# SBPB_FM_v2_3.net
KiCad netlist of a schematic drawn in EAGLE
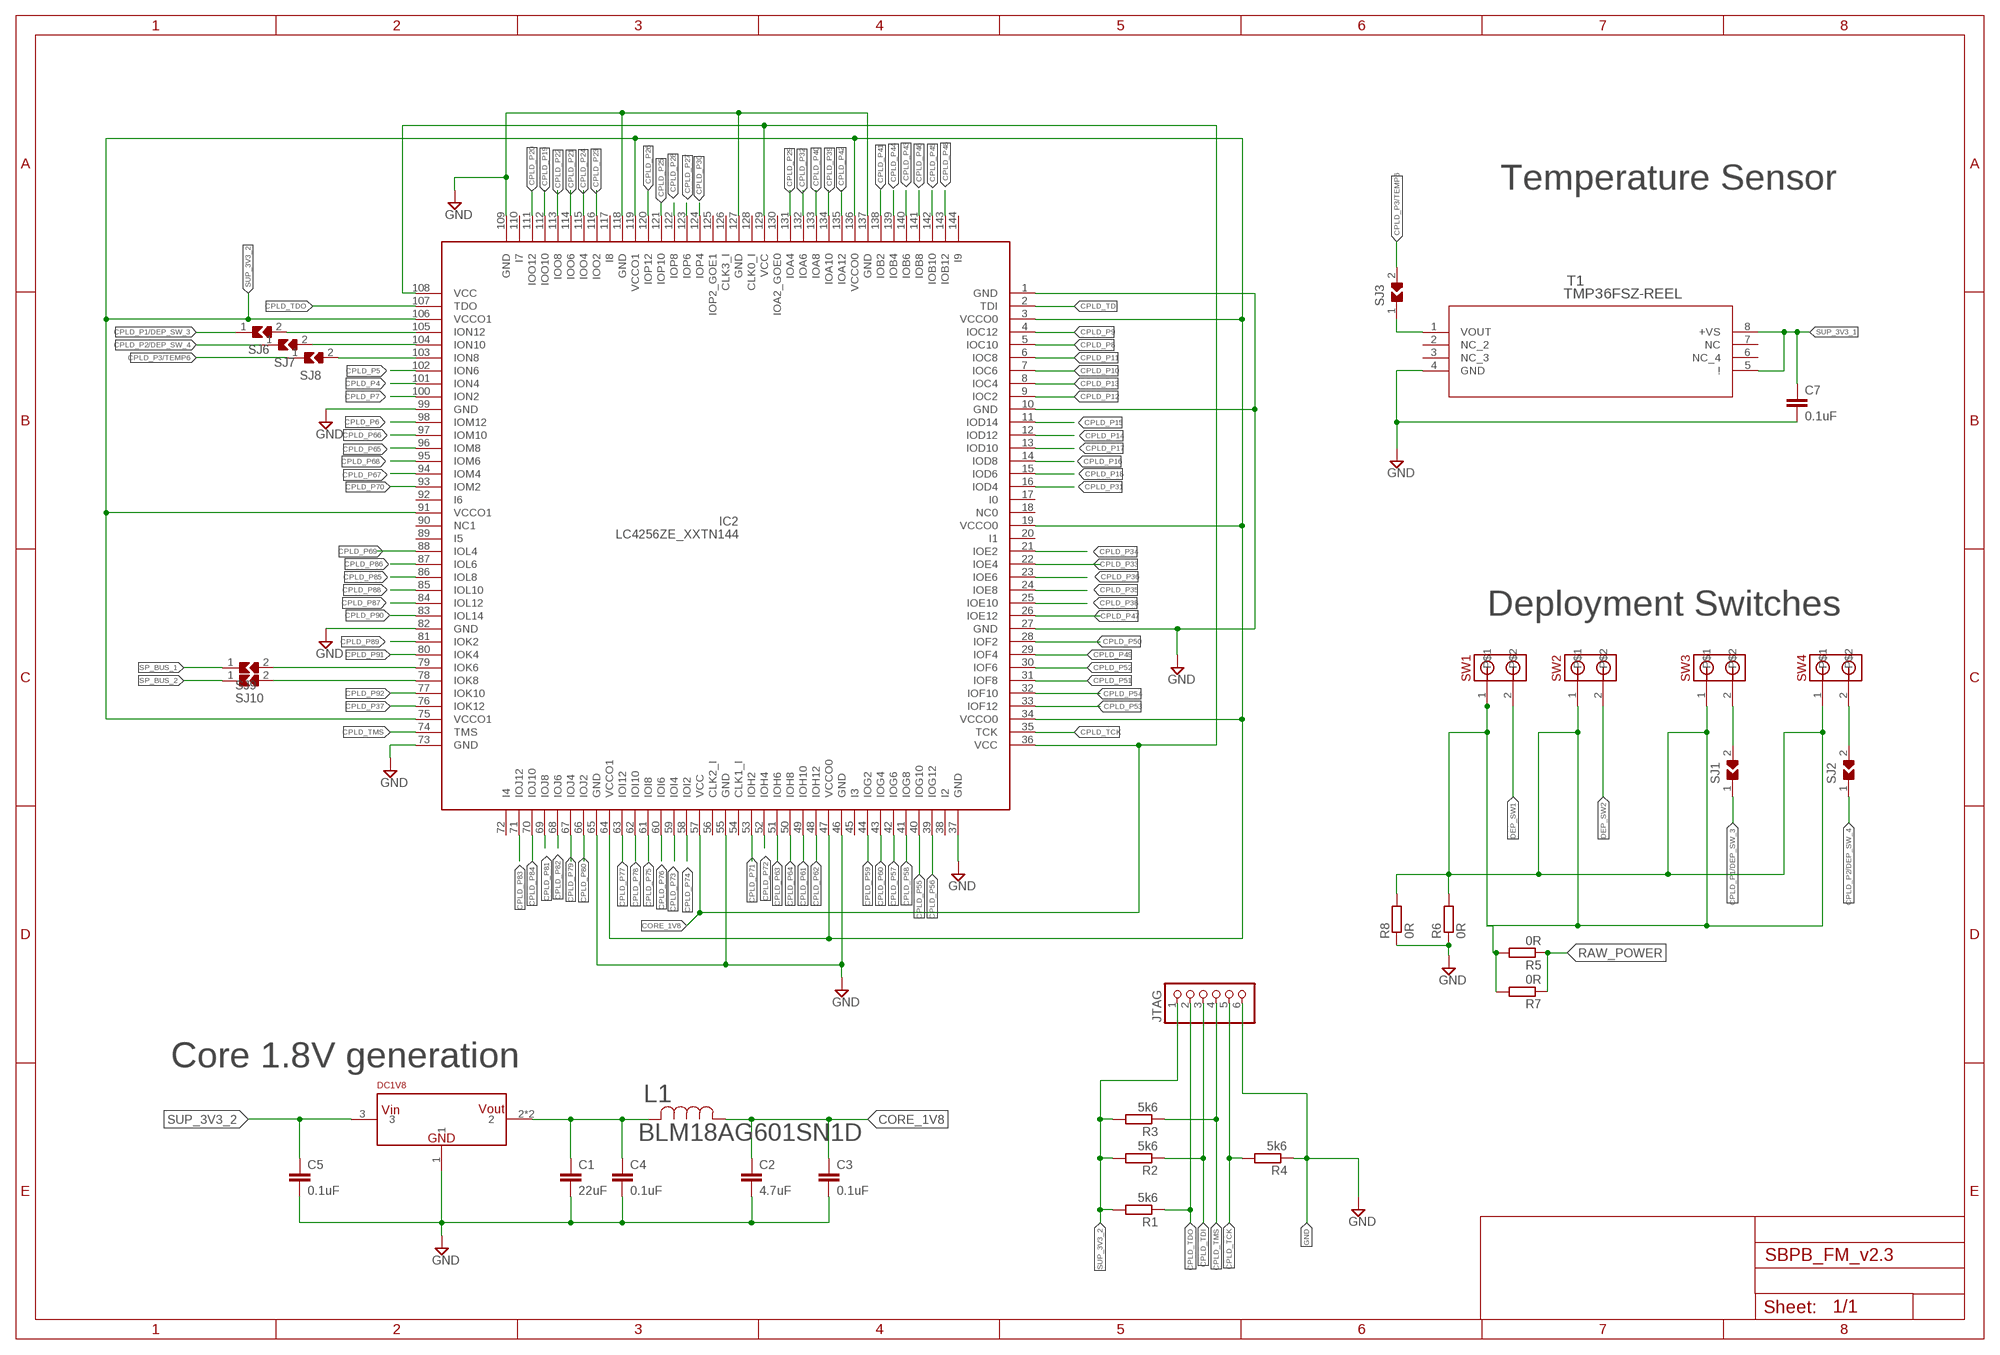
[diagram p0: schematic, sheet 1, part 1 of 2]
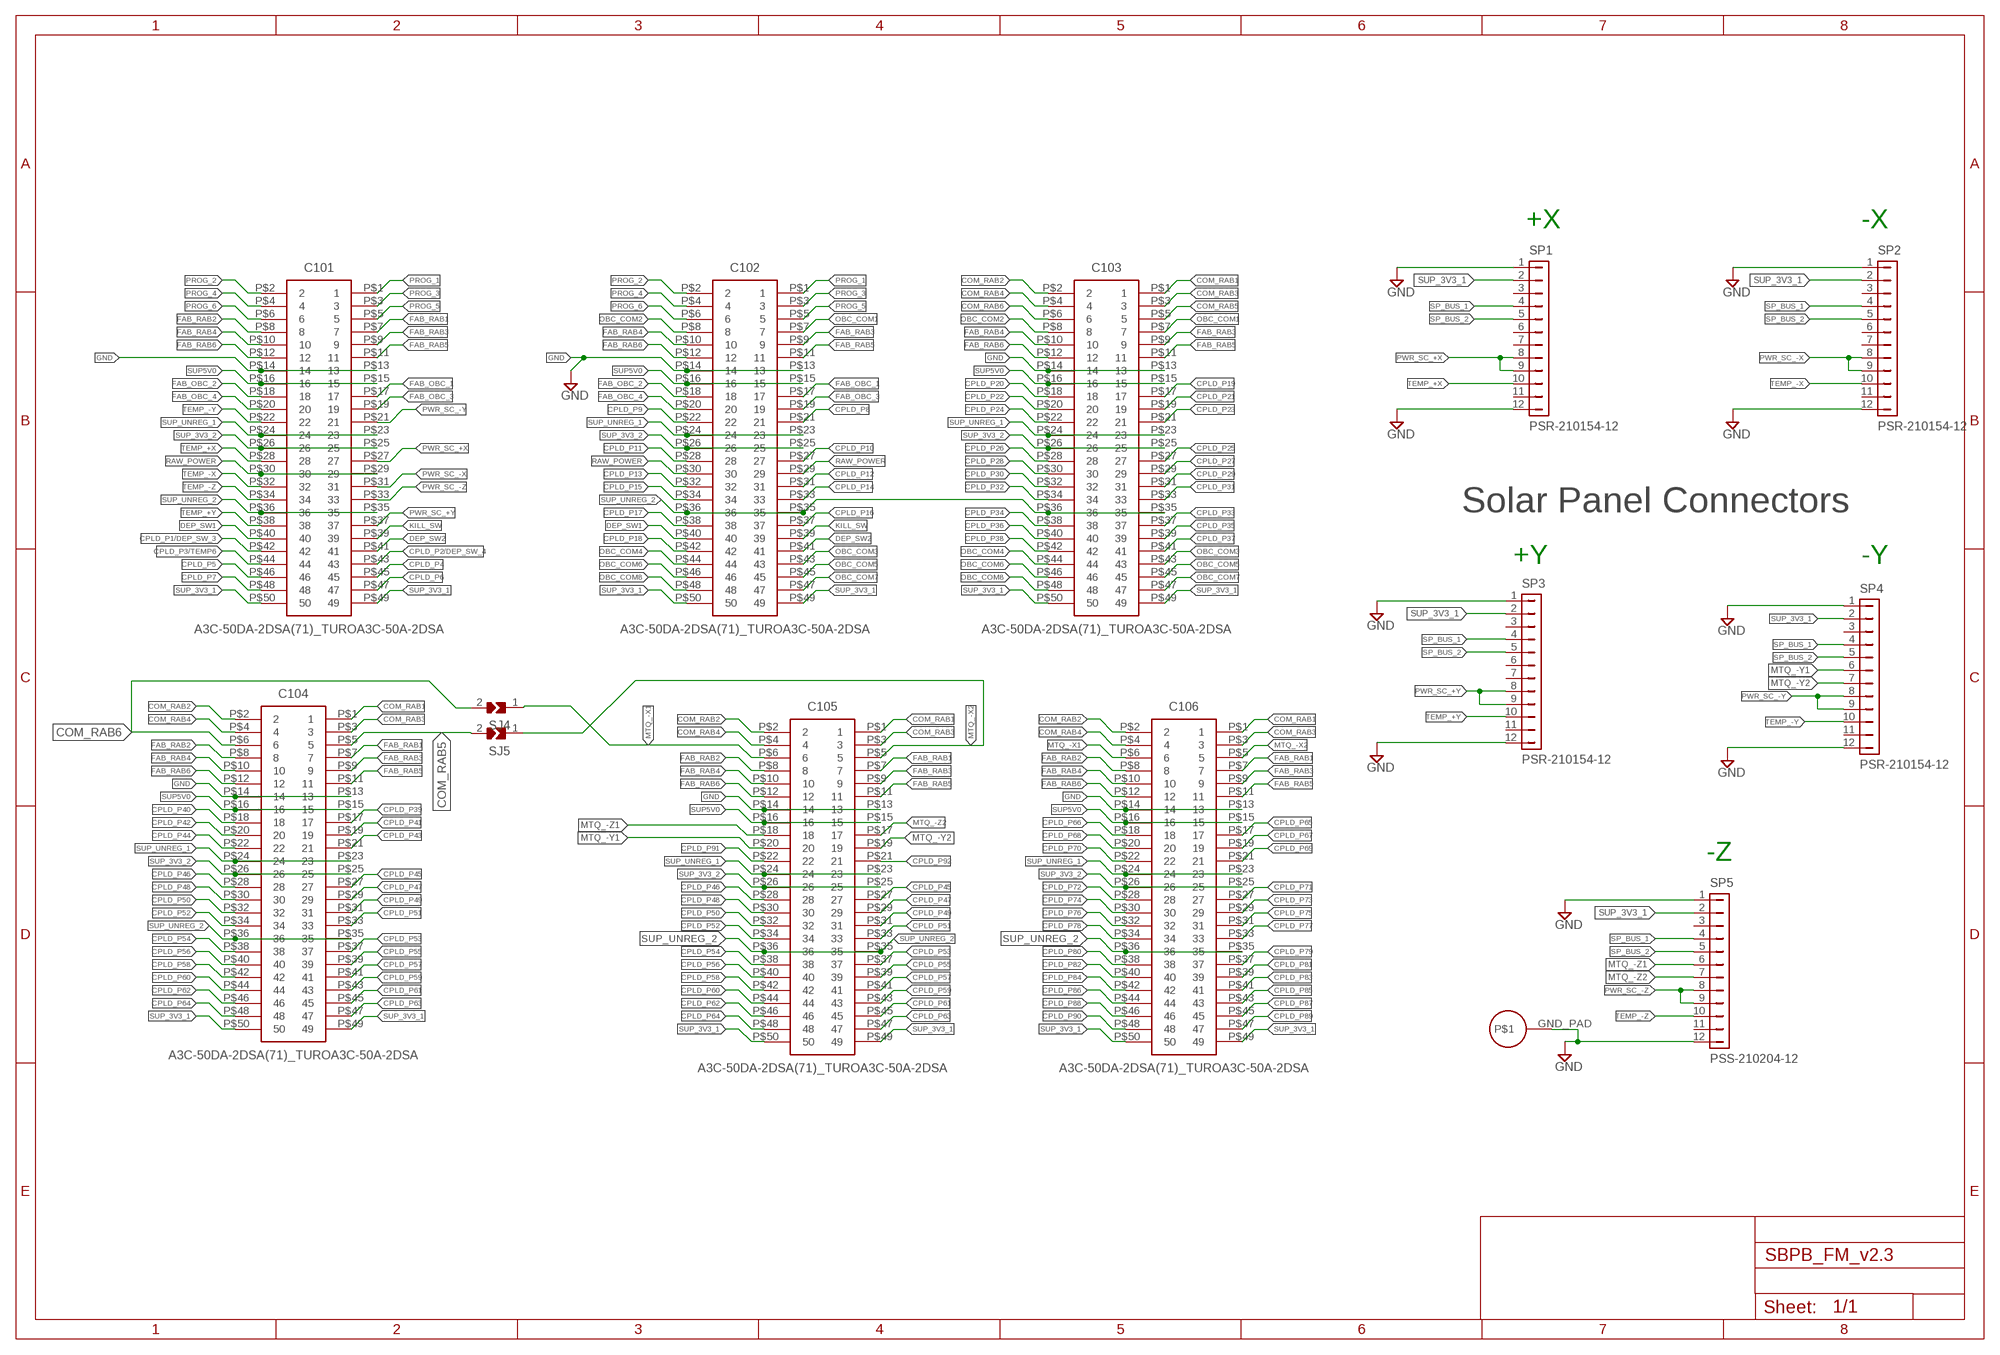
[diagram p1: schematic, sheet 1, part 2 of 2]

(export (version "E")
  (design (tool "Eeschema 10.0.6"))
  (components
    (comp (ref "C1")
      (value "22uF")
      (footprint "eagle-import:C2012")
      (libsource (lib "eagle-import") (part "CC2012"))
    )
    (comp (ref "C2")
      (value "4.7uF")
      (footprint "eagle-import:C2012")
      (libsource (lib "eagle-import") (part "CC2012"))
    )
    (comp (ref "C3")
      (value "0.1uF")
      (footprint "eagle-import:C0402")
      (libsource (lib "eagle-import") (part "CC0402"))
    )
    (comp (ref "C4")
      (value "0.1uF")
      (footprint "eagle-import:C0402")
      (libsource (lib "eagle-import") (part "CC0402"))
    )
    (comp (ref "C5")
      (value "0.1uF")
      (footprint "eagle-import:C0402")
      (libsource (lib "eagle-import") (part "CC0402"))
    )
    (comp (ref "C7")
      (value "0.1uF")
      (footprint "eagle-import:C0402")
      (libsource (lib "eagle-import") (part "CC0402"))
    )
    (comp (ref "C101")
      (value "A3C-50DA-2DSA(71)_TUROA3C-50A-2DSA")
      (footprint "eagle-import:SHDR50W60P200_2X25_5000X400X44_TR")
      (libsource (lib "eagle-import") (part "A3C-50DA-2DSA(71)_TUROA3C-50A-2DSA"))
    )
    (comp (ref "C102")
      (value "A3C-50DA-2DSA(71)_TUROA3C-50A-2DSA")
      (footprint "eagle-import:SHDR50W60P200_2X25_5000X400X44_TR")
      (libsource (lib "eagle-import") (part "A3C-50DA-2DSA(71)_TUROA3C-50A-2DSA"))
    )
    (comp (ref "C103")
      (value "A3C-50DA-2DSA(71)_TUROA3C-50A-2DSA")
      (footprint "eagle-import:SHDR50W60P200_2X25_5000X400X44_TR")
      (libsource (lib "eagle-import") (part "A3C-50DA-2DSA(71)_TUROA3C-50A-2DSA"))
    )
    (comp (ref "C104")
      (value "A3C-50DA-2DSA(71)_TUROA3C-50A-2DSA")
      (footprint "eagle-import:SHDR50W60P200_2X25_5000X400X44_TR")
      (libsource (lib "eagle-import") (part "A3C-50DA-2DSA(71)_TUROA3C-50A-2DSA"))
    )
    (comp (ref "C105")
      (value "A3C-50DA-2DSA(71)_TUROA3C-50A-2DSA")
      (footprint "eagle-import:SHDR50W60P200_2X25_5000X400X44_TR")
      (libsource (lib "eagle-import") (part "A3C-50DA-2DSA(71)_TUROA3C-50A-2DSA"))
    )
    (comp (ref "C106")
      (value "A3C-50DA-2DSA(71)_TUROA3C-50A-2DSA")
      (footprint "eagle-import:SHDR50W60P200_2X25_5000X400X44_TR")
      (libsource (lib "eagle-import") (part "A3C-50DA-2DSA(71)_TUROA3C-50A-2DSA"))
    )
    (comp (ref "DC1V8")
      (value "NCV1117ST18T3G")
      (footprint "eagle-import:SOT223")
      (libsource (lib "eagle-import") (part "NCV1117ST18T3G"))
    )
    (comp (ref "IC2")
      (value "LC4256ZE_XXTN144")
      (footprint "eagle-import:TQFP144")
      (libsource (lib "eagle-import") (part "LC4256ZE_XXTN144"))
    )
    (comp (ref "JTAG")
      (value "PINHD-1X6")
      (footprint "eagle-import:1X06")
      (libsource (lib "eagle-import") (part "PINHD-1X6"))
    )
    (comp (ref "L1")
      (value "BLM18AG601SN1D")
      (footprint "eagle-import:IND_BLM18_0603")
      (libsource (lib "eagle-import") (part "BLM18AG601SN1D"))
    )
    (comp (ref "R1")
      (value "5k6")
      (footprint "eagle-import:R0402")
      (libsource (lib "eagle-import") (part "RR0402"))
    )
    (comp (ref "R2")
      (value "5k6")
      (footprint "eagle-import:R0402")
      (libsource (lib "eagle-import") (part "RR0402"))
    )
    (comp (ref "R3")
      (value "5k6")
      (footprint "eagle-import:R0402")
      (libsource (lib "eagle-import") (part "RR0402"))
    )
    (comp (ref "R4")
      (value "5k6")
      (footprint "eagle-import:R0402")
      (libsource (lib "eagle-import") (part "RR0402"))
    )
    (comp (ref "R5")
      (value "0R")
      (footprint "eagle-import:R3216")
      (libsource (lib "eagle-import") (part "RR3216"))
    )
    (comp (ref "R6")
      (value "0R")
      (footprint "eagle-import:R3216")
      (libsource (lib "eagle-import") (part "RR3216"))
    )
    (comp (ref "R7")
      (value "0R")
      (footprint "eagle-import:R3216")
      (libsource (lib "eagle-import") (part "RR3216"))
    )
    (comp (ref "R8")
      (value "0R")
      (footprint "eagle-import:R3216")
      (libsource (lib "eagle-import") (part "RR3216"))
    )
    (comp (ref "SJ1")
      (value "SJ_BY_TURO")
      (footprint "eagle-import:SJ_TURO")
      (libsource (lib "eagle-import") (part "SJ_BY_TURO"))
    )
    (comp (ref "SJ2")
      (value "0R")
      (footprint "eagle-import:SJ_TURO")
      (libsource (lib "eagle-import") (part "SJ_BY_TURO"))
    )
    (comp (ref "SJ3")
      (value "SJ_BY_TURO")
      (footprint "eagle-import:SJ_TURO")
      (libsource (lib "eagle-import") (part "SJ_BY_TURO"))
    )
    (comp (ref "SJ4")
      (value "SJ_BY_TURO")
      (footprint "eagle-import:SJ_TURO")
      (libsource (lib "eagle-import") (part "SJ_BY_TURO"))
    )
    (comp (ref "SJ5")
      (value "SJ_BY_TURO")
      (footprint "eagle-import:SJ_TURO")
      (libsource (lib "eagle-import") (part "SJ_BY_TURO"))
    )
    (comp (ref "SJ6")
      (value "SJ_BY_TURO")
      (footprint "eagle-import:SJ_TURO")
      (libsource (lib "eagle-import") (part "SJ_BY_TURO"))
    )
    (comp (ref "SJ7")
      (value "SJ_BY_TURO")
      (footprint "eagle-import:SJ_TURO")
      (libsource (lib "eagle-import") (part "SJ_BY_TURO"))
    )
    (comp (ref "SJ8")
      (value "SJ_BY_TURO")
      (footprint "eagle-import:SJ_TURO")
      (libsource (lib "eagle-import") (part "SJ_BY_TURO"))
    )
    (comp (ref "SJ9")
      (value "SJ_BY_TURO")
      (footprint "eagle-import:SJ_TURO")
      (libsource (lib "eagle-import") (part "SJ_BY_TURO"))
    )
    (comp (ref "SJ10")
      (value "SJ_BY_TURO")
      (footprint "eagle-import:SJ_TURO")
      (libsource (lib "eagle-import") (part "SJ_BY_TURO"))
    )
    (comp (ref "SP1")
      (value "PSR-210154-12")
      (footprint "eagle-import:PIN1X12_90")
      (libsource (lib "eagle-import") (part "PSR-210154-12"))
    )
    (comp (ref "SP2")
      (value "PSR-210154-12")
      (footprint "eagle-import:PIN1X12_90")
      (libsource (lib "eagle-import") (part "PSR-210154-12"))
    )
    (comp (ref "SP3")
      (value "PSR-210154-12")
      (footprint "eagle-import:PIN1X12_90")
      (libsource (lib "eagle-import") (part "PSR-210154-12"))
    )
    (comp (ref "SP4")
      (value "PSR-210154-12")
      (footprint "eagle-import:PIN1X12_90")
      (libsource (lib "eagle-import") (part "PSR-210154-12"))
    )
    (comp (ref "SP5")
      (value "PSS-210204-12")
      (footprint "eagle-import:PIN1X12")
      (libsource (lib "eagle-import") (part "PSS-210204-12"))
    )
    (comp (ref "SW1")
      (value "MOLEX-CONN-2-0554600272")
      (footprint "eagle-import:MOLEX-CONN-2-BIRDS")
      (libsource (lib "eagle-import") (part "MOLEX-CONN-2-0554600272"))
    )
    (comp (ref "SW2")
      (value "MOLEX-CONN-2-0554600272")
      (footprint "eagle-import:MOLEX-CONN-2-BIRDS")
      (libsource (lib "eagle-import") (part "MOLEX-CONN-2-0554600272"))
    )
    (comp (ref "SW3")
      (value "MOLEX-CONN-2-0554600272")
      (footprint "eagle-import:MOLEX-CONN-2-BIRDS")
      (libsource (lib "eagle-import") (part "MOLEX-CONN-2-0554600272"))
    )
    (comp (ref "SW4")
      (value "MOLEX-CONN-2-0554600272")
      (footprint "eagle-import:MOLEX-CONN-2-BIRDS")
      (libsource (lib "eagle-import") (part "MOLEX-CONN-2-0554600272"))
    )
    (comp (ref "T1")
      (value "TMP36FSZ-REEL")
      (footprint "eagle-import:R_8")
      (fields (field (name "MANUFACTURER_PART_NUMBER") "TMP36FSZREEL"))
      (libsource (lib "eagle-import") (part "TMP36FSZ-REEL"))
    )
    (comp (ref "U$1")
      (value "GND_PAD")
      (footprint "eagle-import:GND_PAD")
      (libsource (lib "eagle-import") (part "GND_PAD"))
    )
  )
  (nets
    (net (code "1") (name "COM_RAB1") (class "Default")
      (node (ref "C103") (pin "P$1") (pinfunction "1_P$1") (pintype "passive"))
      (node (ref "C104") (pin "P$1") (pinfunction "1_P$1") (pintype "passive"))
      (node (ref "C105") (pin "P$1") (pinfunction "1_P$1") (pintype "passive"))
      (node (ref "C106") (pin "P$1") (pinfunction "1_P$1") (pintype "passive"))
    )
    (net (code "2") (name "COM_RAB2") (class "Default")
      (node (ref "C103") (pin "P$2") (pinfunction "2_P$2") (pintype "passive"))
      (node (ref "C104") (pin "P$2") (pinfunction "2_P$2") (pintype "passive"))
      (node (ref "C105") (pin "P$2") (pinfunction "2_P$2") (pintype "passive"))
      (node (ref "C106") (pin "P$2") (pinfunction "2_P$2") (pintype "passive"))
    )
    (net (code "3") (name "COM_RAB3") (class "Default")
      (node (ref "C103") (pin "P$3") (pinfunction "3_P$3") (pintype "passive"))
      (node (ref "C104") (pin "P$3") (pinfunction "3_P$3") (pintype "passive"))
      (node (ref "C105") (pin "P$3") (pinfunction "3_P$3") (pintype "passive"))
      (node (ref "C106") (pin "P$3") (pinfunction "3_P$3") (pintype "passive"))
    )
    (net (code "4") (name "COM_RAB4") (class "Default")
      (node (ref "C103") (pin "P$4") (pinfunction "4_P$4") (pintype "passive"))
      (node (ref "C104") (pin "P$4") (pinfunction "4_P$4") (pintype "passive"))
      (node (ref "C105") (pin "P$4") (pinfunction "4_P$4") (pintype "passive"))
      (node (ref "C106") (pin "P$4") (pinfunction "4_P$4") (pintype "passive"))
    )
    (net (code "5") (name "COM_RAB5") (class "Default")
      (node (ref "C103") (pin "P$5") (pinfunction "5_P$5") (pintype "passive"))
      (node (ref "C104") (pin "P$5") (pinfunction "5_P$5") (pintype "passive"))
      (node (ref "SJ5") (pin "2") (pinfunction "2_2") (pintype "passive"))
    )
    (net (code "6") (name "COM_RAB6") (class "Default")
      (node (ref "C103") (pin "P$6") (pinfunction "6_P$6") (pintype "passive"))
      (node (ref "C104") (pin "P$6") (pinfunction "6_P$6") (pintype "passive"))
      (node (ref "SJ4") (pin "2") (pinfunction "2_2") (pintype "passive"))
    )
    (net (code "7") (name "CORE_1V8") (class "Default")
      (node (ref "C2") (pin "1") (pinfunction "1_1") (pintype "passive"))
      (node (ref "C3") (pin "1") (pinfunction "1_1") (pintype "passive"))
      (node (ref "IC2") (pin "108") (pinfunction "VCC_108") (pintype "power_in"))
      (node (ref "IC2") (pin "129") (pinfunction "VCC_129") (pintype "power_in"))
      (node (ref "IC2") (pin "36") (pinfunction "VCC_36") (pintype "power_in"))
      (node (ref "IC2") (pin "57") (pinfunction "VCC_57") (pintype "power_in"))
      (node (ref "L1") (pin "1") (pinfunction "1_1") (pintype "passive"))
    )
    (net (code "8") (name "CPLD_P1{slash}DEP_SW_3") (class "Default")
      (node (ref "C101") (pin "P$42") (pinfunction "42_P$42") (pintype "passive"))
      (node (ref "SJ1") (pin "1") (pinfunction "1_1") (pintype "passive"))
      (node (ref "SJ6") (pin "1") (pinfunction "1_1") (pintype "passive"))
    )
    (net (code "9") (name "CPLD_P2{slash}DEP_SW_4") (class "Default")
      (node (ref "C101") (pin "P$43") (pinfunction "43_P$43") (pintype "passive"))
      (node (ref "SJ2") (pin "1") (pinfunction "1_1") (pintype "passive"))
      (node (ref "SJ7") (pin "1") (pinfunction "1_1") (pintype "passive"))
    )
    (net (code "10") (name "CPLD_P3{slash}TEMP6") (class "Default")
      (node (ref "C101") (pin "P$44") (pinfunction "44_P$44") (pintype "passive"))
      (node (ref "SJ3") (pin "2") (pinfunction "2_2") (pintype "passive"))
      (node (ref "SJ8") (pin "1") (pinfunction "1_1") (pintype "passive"))
    )
    (net (code "11") (name "CPLD_P4") (class "Default")
      (node (ref "C101") (pin "P$45") (pinfunction "45_P$45") (pintype "passive"))
      (node (ref "IC2") (pin "101") (pinfunction "ION4_101") (pintype "bidirectional"))
    )
    (net (code "12") (name "CPLD_P5") (class "Default")
      (node (ref "C101") (pin "P$46") (pinfunction "46_P$46") (pintype "passive"))
      (node (ref "IC2") (pin "102") (pinfunction "ION6_102") (pintype "bidirectional"))
    )
    (net (code "13") (name "CPLD_P6") (class "Default")
      (node (ref "C101") (pin "P$47") (pinfunction "47_P$47") (pintype "passive"))
      (node (ref "IC2") (pin "98") (pinfunction "IOM12_98") (pintype "bidirectional"))
    )
    (net (code "14") (name "CPLD_P7") (class "Default")
      (node (ref "C101") (pin "P$48") (pinfunction "48_P$48") (pintype "passive"))
      (node (ref "IC2") (pin "100") (pinfunction "ION2_100") (pintype "bidirectional"))
    )
    (net (code "15") (name "CPLD_P8") (class "Default")
      (node (ref "C102") (pin "P$21") (pinfunction "21_P$21") (pintype "passive"))
      (node (ref "IC2") (pin "5") (pinfunction "IOC10_5") (pintype "bidirectional"))
    )
    (net (code "16") (name "CPLD_P9") (class "Default")
      (node (ref "C102") (pin "P$22") (pinfunction "22_P$22") (pintype "passive"))
      (node (ref "IC2") (pin "4") (pinfunction "IOC12_4") (pintype "bidirectional"))
    )
    (net (code "17") (name "CPLD_P10") (class "Default")
      (node (ref "C102") (pin "P$27") (pinfunction "27_P$27") (pintype "passive"))
      (node (ref "IC2") (pin "7") (pinfunction "IOC6_7") (pintype "bidirectional"))
    )
    (net (code "18") (name "CPLD_P11") (class "Default")
      (node (ref "C102") (pin "P$28") (pinfunction "28_P$28") (pintype "passive"))
      (node (ref "IC2") (pin "6") (pinfunction "IOC8_6") (pintype "bidirectional"))
    )
    (net (code "19") (name "CPLD_P12") (class "Default")
      (node (ref "C102") (pin "P$31") (pinfunction "31_P$31") (pintype "passive"))
      (node (ref "IC2") (pin "9") (pinfunction "IOC2_9") (pintype "bidirectional"))
    )
    (net (code "20") (name "CPLD_P13") (class "Default")
      (node (ref "C102") (pin "P$32") (pinfunction "32_P$32") (pintype "passive"))
      (node (ref "IC2") (pin "8") (pinfunction "IOC4_8") (pintype "bidirectional"))
    )
    (net (code "21") (name "CPLD_P14") (class "Default")
      (node (ref "C102") (pin "P$33") (pinfunction "33_P$33") (pintype "passive"))
      (node (ref "IC2") (pin "12") (pinfunction "IOD12_12") (pintype "bidirectional"))
    )
    (net (code "22") (name "CPLD_P15") (class "Default")
      (node (ref "C102") (pin "P$34") (pinfunction "34_P$34") (pintype "passive"))
      (node (ref "IC2") (pin "11") (pinfunction "IOD14_11") (pintype "bidirectional"))
    )
    (net (code "23") (name "CPLD_P16") (class "Default")
      (node (ref "C102") (pin "P$37") (pinfunction "37_P$37") (pintype "passive"))
      (node (ref "IC2") (pin "14") (pinfunction "IOD8_14") (pintype "bidirectional"))
    )
    (net (code "24") (name "CPLD_P17") (class "Default")
      (node (ref "C102") (pin "P$38") (pinfunction "38_P$38") (pintype "passive"))
      (node (ref "IC2") (pin "13") (pinfunction "IOD10_13") (pintype "bidirectional"))
    )
    (net (code "25") (name "CPLD_P18") (class "Default")
      (node (ref "C102") (pin "P$42") (pinfunction "42_P$42") (pintype "passive"))
      (node (ref "IC2") (pin "15") (pinfunction "IOD6_15") (pintype "bidirectional"))
    )
    (net (code "26") (name "CPLD_P19") (class "Default")
      (node (ref "C103") (pin "P$17") (pinfunction "17_P$17") (pintype "passive"))
      (node (ref "IC2") (pin "112") (pinfunction "IOO10_112") (pintype "bidirectional"))
    )
    (net (code "27") (name "CPLD_P20") (class "Default")
      (node (ref "C103") (pin "P$18") (pinfunction "18_P$18") (pintype "passive"))
      (node (ref "IC2") (pin "111") (pinfunction "IOO12_111") (pintype "bidirectional"))
    )
    (net (code "28") (name "CPLD_P21") (class "Default")
      (node (ref "C103") (pin "P$19") (pinfunction "19_P$19") (pintype "passive"))
      (node (ref "IC2") (pin "114") (pinfunction "IOO6_114") (pintype "bidirectional"))
    )
    (net (code "29") (name "CPLD_P22") (class "Default")
      (node (ref "C103") (pin "P$20") (pinfunction "20_P$20") (pintype "passive"))
      (node (ref "IC2") (pin "113") (pinfunction "IOO8_113") (pintype "bidirectional"))
    )
    (net (code "30") (name "CPLD_P23") (class "Default")
      (node (ref "C103") (pin "P$21") (pinfunction "21_P$21") (pintype "passive"))
      (node (ref "IC2") (pin "116") (pinfunction "IOO2_116") (pintype "bidirectional"))
    )
    (net (code "31") (name "CPLD_P24") (class "Default")
      (node (ref "C103") (pin "P$22") (pinfunction "22_P$22") (pintype "passive"))
      (node (ref "IC2") (pin "115") (pinfunction "IOO4_115") (pintype "bidirectional"))
    )
    (net (code "32") (name "CPLD_P25") (class "Default")
      (node (ref "C103") (pin "P$27") (pinfunction "27_P$27") (pintype "passive"))
      (node (ref "IC2") (pin "121") (pinfunction "IOP10_121") (pintype "bidirectional"))
    )
    (net (code "33") (name "CPLD_P26") (class "Default")
      (node (ref "C103") (pin "P$28") (pinfunction "28_P$28") (pintype "passive"))
      (node (ref "IC2") (pin "120") (pinfunction "IOP12_120") (pintype "bidirectional"))
    )
    (net (code "34") (name "CPLD_P27") (class "Default")
      (node (ref "C103") (pin "P$29") (pinfunction "29_P$29") (pintype "passive"))
      (node (ref "IC2") (pin "123") (pinfunction "IOP6_123") (pintype "bidirectional"))
    )
    (net (code "35") (name "CPLD_P28") (class "Default")
      (node (ref "C103") (pin "P$30") (pinfunction "30_P$30") (pintype "passive"))
      (node (ref "IC2") (pin "122") (pinfunction "IOP8_122") (pintype "bidirectional"))
    )
    (net (code "36") (name "CPLD_P29") (class "Default")
      (node (ref "C103") (pin "P$31") (pinfunction "31_P$31") (pintype "passive"))
      (node (ref "IC2") (pin "131") (pinfunction "IOA4_131") (pintype "bidirectional"))
    )
    (net (code "37") (name "CPLD_P30") (class "Default")
      (node (ref "C103") (pin "P$32") (pinfunction "32_P$32") (pintype "passive"))
      (node (ref "IC2") (pin "124") (pinfunction "IOP4_124") (pintype "bidirectional"))
    )
    (net (code "38") (name "CPLD_P31") (class "Default")
      (node (ref "C103") (pin "P$33") (pinfunction "33_P$33") (pintype "passive"))
      (node (ref "IC2") (pin "16") (pinfunction "IOD4_16") (pintype "bidirectional"))
    )
    (net (code "39") (name "CPLD_P32") (class "Default")
      (node (ref "C103") (pin "P$34") (pinfunction "34_P$34") (pintype "passive"))
      (node (ref "IC2") (pin "132") (pinfunction "IOA6_132") (pintype "bidirectional"))
    )
    (net (code "40") (name "CPLD_P33") (class "Default")
      (node (ref "C103") (pin "P$37") (pinfunction "37_P$37") (pintype "passive"))
      (node (ref "IC2") (pin "22") (pinfunction "IOE4_22") (pintype "bidirectional"))
    )
    (net (code "41") (name "CPLD_P34") (class "Default")
      (node (ref "C103") (pin "P$38") (pinfunction "38_P$38") (pintype "passive"))
      (node (ref "IC2") (pin "21") (pinfunction "IOE2_21") (pintype "bidirectional"))
    )
    (net (code "42") (name "CPLD_P35") (class "Default")
      (node (ref "C103") (pin "P$39") (pinfunction "39_P$39") (pintype "passive"))
      (node (ref "IC2") (pin "24") (pinfunction "IOE8_24") (pintype "bidirectional"))
    )
    (net (code "43") (name "CPLD_P36") (class "Default")
      (node (ref "C103") (pin "P$40") (pinfunction "40_P$40") (pintype "passive"))
      (node (ref "IC2") (pin "23") (pinfunction "IOE6_23") (pintype "bidirectional"))
    )
    (net (code "44") (name "CPLD_P37") (class "Default")
      (node (ref "C103") (pin "P$41") (pinfunction "41_P$41") (pintype "passive"))
      (node (ref "IC2") (pin "76") (pinfunction "IOK12_76") (pintype "bidirectional"))
    )
    (net (code "45") (name "CPLD_P38") (class "Default")
      (node (ref "C103") (pin "P$42") (pinfunction "42_P$42") (pintype "passive"))
      (node (ref "IC2") (pin "25") (pinfunction "IOE10_25") (pintype "bidirectional"))
    )
    (net (code "46") (name "CPLD_P39") (class "Default")
      (node (ref "C104") (pin "P$17") (pinfunction "17_P$17") (pintype "passive"))
      (node (ref "IC2") (pin "134") (pinfunction "IOA10_134") (pintype "bidirectional"))
    )
    (net (code "47") (name "CPLD_P40") (class "Default")
      (node (ref "C104") (pin "P$18") (pinfunction "18_P$18") (pintype "passive"))
      (node (ref "IC2") (pin "133") (pinfunction "IOA8_133") (pintype "bidirectional"))
    )
    (net (code "48") (name "CPLD_P41") (class "Default")
      (node (ref "C104") (pin "P$19") (pinfunction "19_P$19") (pintype "passive"))
      (node (ref "IC2") (pin "138") (pinfunction "IOB2_138") (pintype "bidirectional"))
    )
    (net (code "49") (name "CPLD_P42") (class "Default")
      (node (ref "C104") (pin "P$20") (pinfunction "20_P$20") (pintype "passive"))
      (node (ref "IC2") (pin "135") (pinfunction "IOA12_135") (pintype "bidirectional"))
    )
    (net (code "50") (name "CPLD_P43") (class "Default")
      (node (ref "C104") (pin "P$21") (pinfunction "21_P$21") (pintype "passive"))
      (node (ref "IC2") (pin "140") (pinfunction "IOB6_140") (pintype "bidirectional"))
    )
    (net (code "51") (name "CPLD_P44") (class "Default")
      (node (ref "C104") (pin "P$22") (pinfunction "22_P$22") (pintype "passive"))
      (node (ref "IC2") (pin "139") (pinfunction "IOB4_139") (pintype "bidirectional"))
    )
    (net (code "52") (name "CPLD_P45") (class "Default")
      (node (ref "C104") (pin "P$27") (pinfunction "27_P$27") (pintype "passive"))
      (node (ref "C105") (pin "P$27") (pinfunction "27_P$27") (pintype "passive"))
      (node (ref "IC2") (pin "142") (pinfunction "IOB10_142") (pintype "bidirectional"))
    )
    (net (code "53") (name "CPLD_P46") (class "Default")
      (node (ref "C104") (pin "P$28") (pinfunction "28_P$28") (pintype "passive"))
      (node (ref "C105") (pin "P$28") (pinfunction "28_P$28") (pintype "passive"))
      (node (ref "IC2") (pin "141") (pinfunction "IOB8_141") (pintype "bidirectional"))
    )
    (net (code "54") (name "CPLD_P47") (class "Default")
      (node (ref "C104") (pin "P$29") (pinfunction "29_P$29") (pintype "passive"))
      (node (ref "C105") (pin "P$29") (pinfunction "29_P$29") (pintype "passive"))
      (node (ref "IC2") (pin "26") (pinfunction "IOE12_26") (pintype "bidirectional"))
    )
    (net (code "55") (name "CPLD_P48") (class "Default")
      (node (ref "C104") (pin "P$30") (pinfunction "30_P$30") (pintype "passive"))
      (node (ref "C105") (pin "P$30") (pinfunction "30_P$30") (pintype "passive"))
      (node (ref "IC2") (pin "143") (pinfunction "IOB12_143") (pintype "bidirectional"))
    )
    (net (code "56") (name "CPLD_P49") (class "Default")
      (node (ref "C104") (pin "P$31") (pinfunction "31_P$31") (pintype "passive"))
      (node (ref "C105") (pin "P$31") (pinfunction "31_P$31") (pintype "passive"))
      (node (ref "IC2") (pin "29") (pinfunction "IOF4_29") (pintype "bidirectional"))
    )
    (net (code "57") (name "CPLD_P50") (class "Default")
      (node (ref "C104") (pin "P$32") (pinfunction "32_P$32") (pintype "passive"))
      (node (ref "C105") (pin "P$32") (pinfunction "32_P$32") (pintype "passive"))
      (node (ref "IC2") (pin "28") (pinfunction "IOF2_28") (pintype "bidirectional"))
    )
    (net (code "58") (name "CPLD_P51") (class "Default")
      (node (ref "C104") (pin "P$33") (pinfunction "33_P$33") (pintype "passive"))
      (node (ref "C105") (pin "P$33") (pinfunction "33_P$33") (pintype "passive"))
      (node (ref "IC2") (pin "31") (pinfunction "IOF8_31") (pintype "bidirectional"))
    )
    (net (code "59") (name "CPLD_P52") (class "Default")
      (node (ref "C104") (pin "P$34") (pinfunction "34_P$34") (pintype "passive"))
      (node (ref "C105") (pin "P$34") (pinfunction "34_P$34") (pintype "passive"))
      (node (ref "IC2") (pin "30") (pinfunction "IOF6_30") (pintype "bidirectional"))
    )
    (net (code "60") (name "CPLD_P53") (class "Default")
      (node (ref "C104") (pin "P$37") (pinfunction "37_P$37") (pintype "passive"))
      (node (ref "C105") (pin "P$37") (pinfunction "37_P$37") (pintype "passive"))
      (node (ref "IC2") (pin "33") (pinfunction "IOF12_33") (pintype "bidirectional"))
    )
    (net (code "61") (name "CPLD_P54") (class "Default")
      (node (ref "C104") (pin "P$38") (pinfunction "38_P$38") (pintype "passive"))
      (node (ref "C105") (pin "P$38") (pinfunction "38_P$38") (pintype "passive"))
      (node (ref "IC2") (pin "32") (pinfunction "IOF10_32") (pintype "bidirectional"))
    )
    (net (code "62") (name "CPLD_P55") (class "Default")
      (node (ref "C104") (pin "P$39") (pinfunction "39_P$39") (pintype "passive"))
      (node (ref "C105") (pin "P$39") (pinfunction "39_P$39") (pintype "passive"))
      (node (ref "IC2") (pin "40") (pinfunction "IOG10_40") (pintype "bidirectional"))
    )
    (net (code "63") (name "CPLD_P56") (class "Default")
      (node (ref "C104") (pin "P$40") (pinfunction "40_P$40") (pintype "passive"))
      (node (ref "C105") (pin "P$40") (pinfunction "40_P$40") (pintype "passive"))
      (node (ref "IC2") (pin "39") (pinfunction "IOG12_39") (pintype "bidirectional"))
    )
    (net (code "64") (name "CPLD_P57") (class "Default")
      (node (ref "C104") (pin "P$41") (pinfunction "41_P$41") (pintype "passive"))
      (node (ref "C105") (pin "P$41") (pinfunction "41_P$41") (pintype "passive"))
      (node (ref "IC2") (pin "42") (pinfunction "IOG6_42") (pintype "bidirectional"))
    )
    (net (code "65") (name "CPLD_P58") (class "Default")
      (node (ref "C104") (pin "P$42") (pinfunction "42_P$42") (pintype "passive"))
      (node (ref "C105") (pin "P$42") (pinfunction "42_P$42") (pintype "passive"))
      (node (ref "IC2") (pin "41") (pinfunction "IOG8_41") (pintype "bidirectional"))
    )
    (net (code "66") (name "CPLD_P59") (class "Default")
      (node (ref "C104") (pin "P$43") (pinfunction "43_P$43") (pintype "passive"))
      (node (ref "C105") (pin "P$43") (pinfunction "43_P$43") (pintype "passive"))
      (node (ref "IC2") (pin "44") (pinfunction "IOG2_44") (pintype "bidirectional"))
    )
    (net (code "67") (name "CPLD_P60") (class "Default")
      (node (ref "C104") (pin "P$44") (pinfunction "44_P$44") (pintype "passive"))
      (node (ref "C105") (pin "P$44") (pinfunction "44_P$44") (pintype "passive"))
      (node (ref "IC2") (pin "43") (pinfunction "IOG4_43") (pintype "bidirectional"))
    )
    (net (code "68") (name "CPLD_P61") (class "Default")
      (node (ref "C104") (pin "P$45") (pinfunction "45_P$45") (pintype "passive"))
      (node (ref "C105") (pin "P$45") (pinfunction "45_P$45") (pintype "passive"))
      (node (ref "IC2") (pin "49") (pinfunction "IOH10_49") (pintype "bidirectional"))
    )
    (net (code "69") (name "CPLD_P62") (class "Default")
      (node (ref "C104") (pin "P$46") (pinfunction "46_P$46") (pintype "passive"))
      (node (ref "C105") (pin "P$46") (pinfunction "46_P$46") (pintype "passive"))
      (node (ref "IC2") (pin "48") (pinfunction "IOH12_48") (pintype "bidirectional"))
    )
    (net (code "70") (name "CPLD_P63") (class "Default")
      (node (ref "C104") (pin "P$47") (pinfunction "47_P$47") (pintype "passive"))
      (node (ref "C105") (pin "P$47") (pinfunction "47_P$47") (pintype "passive"))
      (node (ref "IC2") (pin "51") (pinfunction "IOH6_51") (pintype "bidirectional"))
    )
    (net (code "71") (name "CPLD_P64") (class "Default")
      (node (ref "C104") (pin "P$48") (pinfunction "48_P$48") (pintype "passive"))
      (node (ref "C105") (pin "P$48") (pinfunction "48_P$48") (pintype "passive"))
      (node (ref "IC2") (pin "50") (pinfunction "IOH8_50") (pintype "bidirectional"))
    )
    (net (code "72") (name "CPLD_P65") (class "Default")
      (node (ref "C106") (pin "P$17") (pinfunction "17_P$17") (pintype "passive"))
      (node (ref "IC2") (pin "96") (pinfunction "IOM8_96") (pintype "bidirectional"))
    )
    (net (code "73") (name "CPLD_P66") (class "Default")
      (node (ref "C106") (pin "P$18") (pinfunction "18_P$18") (pintype "passive"))
      (node (ref "IC2") (pin "97") (pinfunction "IOM10_97") (pintype "bidirectional"))
    )
    (net (code "74") (name "CPLD_P67") (class "Default")
      (node (ref "C106") (pin "P$19") (pinfunction "19_P$19") (pintype "passive"))
      (node (ref "IC2") (pin "94") (pinfunction "IOM4_94") (pintype "bidirectional"))
    )
    (net (code "75") (name "CPLD_P68") (class "Default")
      (node (ref "C106") (pin "P$20") (pinfunction "20_P$20") (pintype "passive"))
      (node (ref "IC2") (pin "95") (pinfunction "IOM6_95") (pintype "bidirectional"))
    )
    (net (code "76") (name "CPLD_P69") (class "Default")
      (node (ref "C106") (pin "P$21") (pinfunction "21_P$21") (pintype "passive"))
      (node (ref "IC2") (pin "88") (pinfunction "IOL4_88") (pintype "bidirectional"))
    )
    (net (code "77") (name "CPLD_P70") (class "Default")
      (node (ref "C106") (pin "P$22") (pinfunction "22_P$22") (pintype "passive"))
      (node (ref "IC2") (pin "93") (pinfunction "IOM2_93") (pintype "bidirectional"))
    )
    (net (code "78") (name "CPLD_P71") (class "Default")
      (node (ref "C106") (pin "P$27") (pinfunction "27_P$27") (pintype "passive"))
      (node (ref "IC2") (pin "53") (pinfunction "IOH2_53") (pintype "bidirectional"))
    )
    (net (code "79") (name "CPLD_P72") (class "Default")
      (node (ref "C106") (pin "P$28") (pinfunction "28_P$28") (pintype "passive"))
      (node (ref "IC2") (pin "52") (pinfunction "IOH4_52") (pintype "bidirectional"))
    )
    (net (code "80") (name "CPLD_P73") (class "Default")
      (node (ref "C106") (pin "P$29") (pinfunction "29_P$29") (pintype "passive"))
      (node (ref "IC2") (pin "59") (pinfunction "IOI4_59") (pintype "bidirectional"))
    )
    (net (code "81") (name "CPLD_P74") (class "Default")
      (node (ref "C106") (pin "P$30") (pinfunction "30_P$30") (pintype "passive"))
      (node (ref "IC2") (pin "58") (pinfunction "IOI2_58") (pintype "bidirectional"))
    )
    (net (code "82") (name "CPLD_P75") (class "Default")
      (node (ref "C106") (pin "P$31") (pinfunction "31_P$31") (pintype "passive"))
      (node (ref "IC2") (pin "61") (pinfunction "IOI8_61") (pintype "bidirectional"))
    )
    (net (code "83") (name "CPLD_P76") (class "Default")
      (node (ref "C106") (pin "P$32") (pinfunction "32_P$32") (pintype "passive"))
      (node (ref "IC2") (pin "60") (pinfunction "IOI6_60") (pintype "bidirectional"))
    )
    (net (code "84") (name "CPLD_P77") (class "Default")
      (node (ref "C106") (pin "P$33") (pinfunction "33_P$33") (pintype "passive"))
      (node (ref "IC2") (pin "63") (pinfunction "IOI12_63") (pintype "bidirectional"))
    )
    (net (code "85") (name "CPLD_P78") (class "Default")
      (node (ref "C106") (pin "P$34") (pinfunction "34_P$34") (pintype "passive"))
      (node (ref "IC2") (pin "62") (pinfunction "IOI10_62") (pintype "bidirectional"))
    )
    (net (code "86") (name "CPLD_P79") (class "Default")
      (node (ref "C106") (pin "P$37") (pinfunction "37_P$37") (pintype "passive"))
      (node (ref "IC2") (pin "67") (pinfunction "IOJ4_67") (pintype "bidirectional"))
    )
    (net (code "87") (name "CPLD_P80") (class "Default")
      (node (ref "C106") (pin "P$38") (pinfunction "38_P$38") (pintype "passive"))
      (node (ref "IC2") (pin "66") (pinfunction "IOJ2_66") (pintype "bidirectional"))
    )
    (net (code "88") (name "CPLD_P81") (class "Default")
      (node (ref "C106") (pin "P$39") (pinfunction "39_P$39") (pintype "passive"))
      (node (ref "IC2") (pin "69") (pinfunction "IOJ8_69") (pintype "bidirectional"))
    )
    (net (code "89") (name "CPLD_P82") (class "Default")
      (node (ref "C106") (pin "P$40") (pinfunction "40_P$40") (pintype "passive"))
      (node (ref "IC2") (pin "68") (pinfunction "IOJ6_68") (pintype "bidirectional"))
    )
    (net (code "90") (name "CPLD_P83") (class "Default")
      (node (ref "C106") (pin "P$41") (pinfunction "41_P$41") (pintype "passive"))
      (node (ref "IC2") (pin "71") (pinfunction "IOJ12_71") (pintype "bidirectional"))
    )
    (net (code "91") (name "CPLD_P84") (class "Default")
      (node (ref "C106") (pin "P$42") (pinfunction "42_P$42") (pintype "passive"))
      (node (ref "IC2") (pin "70") (pinfunction "IOJ10_70") (pintype "bidirectional"))
    )
    (net (code "92") (name "CPLD_P85") (class "Default")
      (node (ref "C106") (pin "P$43") (pinfunction "43_P$43") (pintype "passive"))
      (node (ref "IC2") (pin "86") (pinfunction "IOL8_86") (pintype "bidirectional"))
    )
    (net (code "93") (name "CPLD_P86") (class "Default")
      (node (ref "C106") (pin "P$44") (pinfunction "44_P$44") (pintype "passive"))
      (node (ref "IC2") (pin "87") (pinfunction "IOL6_87") (pintype "bidirectional"))
    )
    (net (code "94") (name "CPLD_P87") (class "Default")
      (node (ref "C106") (pin "P$45") (pinfunction "45_P$45") (pintype "passive"))
      (node (ref "IC2") (pin "84") (pinfunction "IOL12_84") (pintype "bidirectional"))
    )
    (net (code "95") (name "CPLD_P88") (class "Default")
      (node (ref "C106") (pin "P$46") (pinfunction "46_P$46") (pintype "passive"))
      (node (ref "IC2") (pin "85") (pinfunction "IOL10_85") (pintype "bidirectional"))
    )
    (net (code "96") (name "CPLD_P89") (class "Default")
      (node (ref "C106") (pin "P$47") (pinfunction "47_P$47") (pintype "passive"))
      (node (ref "IC2") (pin "81") (pinfunction "IOK2_81") (pintype "bidirectional"))
    )
    (net (code "97") (name "CPLD_P90") (class "Default")
      (node (ref "C106") (pin "P$48") (pinfunction "48_P$48") (pintype "passive"))
      (node (ref "IC2") (pin "83") (pinfunction "IOL14_83") (pintype "bidirectional"))
    )
    (net (code "98") (name "CPLD_P91") (class "Default")
      (node (ref "C105") (pin "P$22") (pinfunction "22_P$22") (pintype "passive"))
      (node (ref "IC2") (pin "80") (pinfunction "IOK4_80") (pintype "bidirectional"))
    )
    (net (code "99") (name "CPLD_P92") (class "Default")
      (node (ref "C105") (pin "P$21") (pinfunction "21_P$21") (pintype "passive"))
      (node (ref "IC2") (pin "77") (pinfunction "IOK10_77") (pintype "bidirectional"))
    )
    (net (code "100") (name "CPLD_TCK") (class "Default")
      (node (ref "IC2") (pin "35") (pinfunction "TCK_35") (pintype "input"))
      (node (ref "JTAG") (pin "5") (pinfunction "5_5") (pintype "passive"))
      (node (ref "R4") (pin "2") (pinfunction "2_2") (pintype "passive"))
    )
    (net (code "101") (name "CPLD_TDI") (class "Default")
      (node (ref "IC2") (pin "2") (pinfunction "TDI_2") (pintype "input"))
      (node (ref "JTAG") (pin "3") (pinfunction "3_3") (pintype "passive"))
      (node (ref "R2") (pin "1") (pinfunction "1_1") (pintype "passive"))
    )
    (net (code "102") (name "CPLD_TDO") (class "Default")
      (node (ref "IC2") (pin "107") (pinfunction "TDO_107") (pintype "output"))
      (node (ref "JTAG") (pin "2") (pinfunction "2_2") (pintype "passive"))
      (node (ref "R1") (pin "1") (pinfunction "1_1") (pintype "passive"))
    )
    (net (code "103") (name "CPLD_TMS") (class "Default")
      (node (ref "IC2") (pin "74") (pinfunction "TMS_74") (pintype "input"))
      (node (ref "JTAG") (pin "4") (pinfunction "4_4") (pintype "passive"))
      (node (ref "R3") (pin "1") (pinfunction "1_1") (pintype "passive"))
    )
    (net (code "104") (name "DEP_SW1") (class "Default")
      (node (ref "C101") (pin "P$40") (pinfunction "40_P$40") (pintype "passive"))
      (node (ref "C102") (pin "P$40") (pinfunction "40_P$40") (pintype "passive"))
      (node (ref "SW1") (pin "2") (pinfunction "P$2_2") (pintype "bidirectional"))
    )
    (net (code "105") (name "DEP_SW2") (class "Default")
      (node (ref "C101") (pin "P$41") (pinfunction "41_P$41") (pintype "passive"))
      (node (ref "C102") (pin "P$41") (pinfunction "41_P$41") (pintype "passive"))
      (node (ref "SW2") (pin "2") (pinfunction "P$2_2") (pintype "bidirectional"))
    )
    (net (code "106") (name "FAB_OBC_1") (class "Default")
      (node (ref "C101") (pin "P$17") (pinfunction "17_P$17") (pintype "passive"))
      (node (ref "C102") (pin "P$17") (pinfunction "17_P$17") (pintype "passive"))
    )
    (net (code "107") (name "FAB_OBC_2") (class "Default")
      (node (ref "C101") (pin "P$18") (pinfunction "18_P$18") (pintype "passive"))
      (node (ref "C102") (pin "P$18") (pinfunction "18_P$18") (pintype "passive"))
    )
    (net (code "108") (name "FAB_OBC_3") (class "Default")
      (node (ref "C101") (pin "P$19") (pinfunction "19_P$19") (pintype "passive"))
      (node (ref "C102") (pin "P$19") (pinfunction "19_P$19") (pintype "passive"))
    )
    (net (code "109") (name "FAB_OBC_4") (class "Default")
      (node (ref "C101") (pin "P$20") (pinfunction "20_P$20") (pintype "passive"))
      (node (ref "C102") (pin "P$20") (pinfunction "20_P$20") (pintype "passive"))
    )
    (net (code "110") (name "FAB_RAB1") (class "Default")
      (node (ref "C101") (pin "P$7") (pinfunction "7_P$7") (pintype "passive"))
      (node (ref "C104") (pin "P$7") (pinfunction "7_P$7") (pintype "passive"))
      (node (ref "C105") (pin "P$7") (pinfunction "7_P$7") (pintype "passive"))
      (node (ref "C106") (pin "P$7") (pinfunction "7_P$7") (pintype "passive"))
    )
    (net (code "111") (name "FAB_RAB2") (class "Default")
      (node (ref "C101") (pin "P$8") (pinfunction "8_P$8") (pintype "passive"))
      (node (ref "C104") (pin "P$8") (pinfunction "8_P$8") (pintype "passive"))
      (node (ref "C105") (pin "P$8") (pinfunction "8_P$8") (pintype "passive"))
      (node (ref "C106") (pin "P$8") (pinfunction "8_P$8") (pintype "passive"))
    )
    (net (code "112") (name "FAB_RAB3") (class "Default")
      (node (ref "C101") (pin "P$9") (pinfunction "9_P$9") (pintype "passive"))
      (node (ref "C102") (pin "P$9") (pinfunction "9_P$9") (pintype "passive"))
      (node (ref "C103") (pin "P$9") (pinfunction "9_P$9") (pintype "passive"))
      (node (ref "C104") (pin "P$9") (pinfunction "9_P$9") (pintype "passive"))
      (node (ref "C105") (pin "P$9") (pinfunction "9_P$9") (pintype "passive"))
      (node (ref "C106") (pin "P$9") (pinfunction "9_P$9") (pintype "passive"))
    )
    (net (code "113") (name "FAB_RAB4") (class "Default")
      (node (ref "C101") (pin "P$10") (pinfunction "10_P$10") (pintype "passive"))
      (node (ref "C102") (pin "P$10") (pinfunction "10_P$10") (pintype "passive"))
      (node (ref "C103") (pin "P$10") (pinfunction "10_P$10") (pintype "passive"))
      (node (ref "C104") (pin "P$10") (pinfunction "10_P$10") (pintype "passive"))
      (node (ref "C105") (pin "P$10") (pinfunction "10_P$10") (pintype "passive"))
      (node (ref "C106") (pin "P$10") (pinfunction "10_P$10") (pintype "passive"))
    )
    (net (code "114") (name "FAB_RAB5") (class "Default")
      (node (ref "C101") (pin "P$11") (pinfunction "11_P$11") (pintype "passive"))
      (node (ref "C102") (pin "P$11") (pinfunction "11_P$11") (pintype "passive"))
      (node (ref "C103") (pin "P$11") (pinfunction "11_P$11") (pintype "passive"))
      (node (ref "C104") (pin "P$11") (pinfunction "11_P$11") (pintype "passive"))
      (node (ref "C105") (pin "P$11") (pinfunction "11_P$11") (pintype "passive"))
      (node (ref "C106") (pin "P$11") (pinfunction "11_P$11") (pintype "passive"))
    )
    (net (code "115") (name "FAB_RAB6") (class "Default")
      (node (ref "C101") (pin "P$12") (pinfunction "12_P$12") (pintype "passive"))
      (node (ref "C102") (pin "P$12") (pinfunction "12_P$12") (pintype "passive"))
      (node (ref "C103") (pin "P$12") (pinfunction "12_P$12") (pintype "passive"))
      (node (ref "C104") (pin "P$12") (pinfunction "12_P$12") (pintype "passive"))
      (node (ref "C105") (pin "P$12") (pinfunction "12_P$12") (pintype "passive"))
      (node (ref "C106") (pin "P$12") (pinfunction "12_P$12") (pintype "passive"))
    )
    (net (code "116") (name "GND") (class "Default")
      (node (ref "C1") (pin "2") (pinfunction "2_2") (pintype "passive"))
      (node (ref "C101") (pin "P$13") (pinfunction "13_P$13") (pintype "passive"))
      (node (ref "C101") (pin "P$14") (pinfunction "14_P$14") (pintype "passive"))
      (node (ref "C102") (pin "P$13") (pinfunction "13_P$13") (pintype "passive"))
      (node (ref "C102") (pin "P$14") (pinfunction "14_P$14") (pintype "passive"))
      (node (ref "C103") (pin "P$13") (pinfunction "13_P$13") (pintype "passive"))
      (node (ref "C103") (pin "P$14") (pinfunction "14_P$14") (pintype "passive"))
      (node (ref "C104") (pin "P$13") (pinfunction "13_P$13") (pintype "passive"))
      (node (ref "C104") (pin "P$14") (pinfunction "14_P$14") (pintype "passive"))
      (node (ref "C105") (pin "P$13") (pinfunction "13_P$13") (pintype "passive"))
      (node (ref "C105") (pin "P$14") (pinfunction "14_P$14") (pintype "passive"))
      (node (ref "C106") (pin "P$13") (pinfunction "13_P$13") (pintype "passive"))
      (node (ref "C106") (pin "P$14") (pinfunction "14_P$14") (pintype "passive"))
      (node (ref "C2") (pin "2") (pinfunction "2_2") (pintype "passive"))
      (node (ref "C3") (pin "2") (pinfunction "2_2") (pintype "passive"))
      (node (ref "C4") (pin "2") (pinfunction "2_2") (pintype "passive"))
      (node (ref "C5") (pin "2") (pinfunction "2_2") (pintype "passive"))
      (node (ref "C7") (pin "2") (pinfunction "2_2") (pintype "passive"))
      (node (ref "DC1V8") (pin "1") (pinfunction "1_1") (pintype "bidirectional"))
      (node (ref "IC2") (pin "1") (pinfunction "GND_1") (pintype "power_in"))
      (node (ref "IC2") (pin "10") (pinfunction "GND_10") (pintype "power_in"))
      (node (ref "IC2") (pin "109") (pinfunction "GND_109") (pintype "power_in"))
      (node (ref "IC2") (pin "118") (pinfunction "GND_118") (pintype "power_in"))
      (node (ref "IC2") (pin "127") (pinfunction "GND_127") (pintype "power_in"))
      (node (ref "IC2") (pin "137") (pinfunction "GND_137") (pintype "power_in"))
      (node (ref "IC2") (pin "27") (pinfunction "GND_27") (pintype "power_in"))
      (node (ref "IC2") (pin "37") (pinfunction "GND_37") (pintype "power_in"))
      (node (ref "IC2") (pin "46") (pinfunction "GND_46") (pintype "power_in"))
      (node (ref "IC2") (pin "55") (pinfunction "GND_55") (pintype "power_in"))
      (node (ref "IC2") (pin "65") (pinfunction "GND_65") (pintype "power_in"))
      (node (ref "IC2") (pin "73") (pinfunction "GND_73") (pintype "power_in"))
      (node (ref "IC2") (pin "82") (pinfunction "GND_82") (pintype "power_in"))
      (node (ref "IC2") (pin "99") (pinfunction "GND_99") (pintype "power_in"))
      (node (ref "JTAG") (pin "6") (pinfunction "6_6") (pintype "passive"))
      (node (ref "R4") (pin "1") (pinfunction "1_1") (pintype "passive"))
      (node (ref "R6") (pin "1") (pinfunction "1_1") (pintype "passive"))
      (node (ref "R8") (pin "1") (pinfunction "1_1") (pintype "passive"))
      (node (ref "SP1") (pin "1") (pinfunction "1_1") (pintype "passive"))
      (node (ref "SP1") (pin "12") (pinfunction "12_12") (pintype "passive"))
      (node (ref "SP2") (pin "1") (pinfunction "1_1") (pintype "passive"))
      (node (ref "SP2") (pin "12") (pinfunction "12_12") (pintype "passive"))
      (node (ref "SP3") (pin "1") (pinfunction "1_1") (pintype "passive"))
      (node (ref "SP3") (pin "12") (pinfunction "12_12") (pintype "passive"))
      (node (ref "SP4") (pin "1") (pinfunction "1_1") (pintype "passive"))
      (node (ref "SP4") (pin "12") (pinfunction "12_12") (pintype "passive"))
      (node (ref "SP5") (pin "1") (pinfunction "1_1") (pintype "passive"))
      (node (ref "SP5") (pin "12") (pinfunction "12_12") (pintype "passive"))
      (node (ref "T1") (pin "4") (pinfunction "GND_4") (pintype "passive"))
      (node (ref "U$1") (pin "GND_PAD") (pinfunction "P$1_GND_PAD") (pintype "bidirectional"))
    )
    (net (code "117") (name "KILL_SW") (class "Default")
      (node (ref "C101") (pin "P$39") (pinfunction "39_P$39") (pintype "passive"))
      (node (ref "C102") (pin "P$39") (pinfunction "39_P$39") (pintype "passive"))
    )
    (net (code "118") (name "MTQ_-X1") (class "Default")
      (node (ref "C105") (pin "P$6") (pinfunction "6_P$6") (pintype "passive"))
      (node (ref "C106") (pin "P$6") (pinfunction "6_P$6") (pintype "passive"))
      (node (ref "SJ4") (pin "1") (pinfunction "1_1") (pintype "passive"))
    )
    (net (code "119") (name "MTQ_-X2") (class "Default")
      (node (ref "C105") (pin "P$5") (pinfunction "5_P$5") (pintype "passive"))
      (node (ref "C106") (pin "P$5") (pinfunction "5_P$5") (pintype "passive"))
      (node (ref "SJ5") (pin "1") (pinfunction "1_1") (pintype "passive"))
    )
    (net (code "120") (name "MTQ_-Y1") (class "Default")
      (node (ref "C105") (pin "P$20") (pinfunction "20_P$20") (pintype "passive"))
      (node (ref "SP4") (pin "6") (pinfunction "6_6") (pintype "passive"))
    )
    (net (code "121") (name "MTQ_-Y2") (class "Default")
      (node (ref "C105") (pin "P$19") (pinfunction "19_P$19") (pintype "passive"))
      (node (ref "SP4") (pin "7") (pinfunction "7_7") (pintype "passive"))
    )
    (net (code "122") (name "MTQ_-Z1") (class "Default")
      (node (ref "C105") (pin "P$18") (pinfunction "18_P$18") (pintype "passive"))
      (node (ref "SP5") (pin "6") (pinfunction "6_6") (pintype "passive"))
    )
    (net (code "123") (name "MTQ_-Z2") (class "Default")
      (node (ref "C105") (pin "P$17") (pinfunction "17_P$17") (pintype "passive"))
      (node (ref "SP5") (pin "7") (pinfunction "7_7") (pintype "passive"))
    )
    (net (code "124") (name "Net-(C1-Pad1)") (class "Default")
      (node (ref "C1") (pin "1") (pinfunction "1_1") (pintype "passive"))
      (node (ref "C4") (pin "1") (pinfunction "1_1") (pintype "passive"))
      (node (ref "DC1V8") (pin "2") (pinfunction "2_2") (pintype "bidirectional"))
      (node (ref "DC1V8") (pin "4") (pinfunction "2_4") (pintype "bidirectional"))
      (node (ref "L1") (pin "2") (pinfunction "2_2") (pintype "passive"))
    )
    (net (code "125") (name "Net-(IC2-IOK6)") (class "Default")
      (node (ref "IC2") (pin "79") (pinfunction "IOK6_79") (pintype "bidirectional"))
      (node (ref "SJ9") (pin "2") (pinfunction "2_2") (pintype "passive"))
    )
    (net (code "126") (name "Net-(IC2-IOK8)") (class "Default")
      (node (ref "IC2") (pin "78") (pinfunction "IOK8_78") (pintype "bidirectional"))
      (node (ref "SJ10") (pin "2") (pinfunction "2_2") (pintype "passive"))
    )
    (net (code "127") (name "Net-(IC2-ION8)") (class "Default")
      (node (ref "IC2") (pin "103") (pinfunction "ION8_103") (pintype "bidirectional"))
      (node (ref "SJ8") (pin "2") (pinfunction "2_2") (pintype "passive"))
    )
    (net (code "128") (name "Net-(IC2-ION10)") (class "Default")
      (node (ref "IC2") (pin "104") (pinfunction "ION10_104") (pintype "bidirectional"))
      (node (ref "SJ7") (pin "2") (pinfunction "2_2") (pintype "passive"))
    )
    (net (code "129") (name "Net-(IC2-ION12)") (class "Default")
      (node (ref "IC2") (pin "105") (pinfunction "ION12_105") (pintype "bidirectional"))
      (node (ref "SJ6") (pin "2") (pinfunction "2_2") (pintype "passive"))
    )
    (net (code "130") (name "Net-(SW1-P$1)") (class "Default")
      (node (ref "R5") (pin "2") (pinfunction "2_2") (pintype "passive"))
      (node (ref "R6") (pin "2") (pinfunction "2_2") (pintype "passive"))
      (node (ref "R7") (pin "2") (pinfunction "2_2") (pintype "passive"))
      (node (ref "R8") (pin "2") (pinfunction "2_2") (pintype "passive"))
      (node (ref "SW1") (pin "1") (pinfunction "P$1_1") (pintype "bidirectional"))
      (node (ref "SW2") (pin "1") (pinfunction "P$1_1") (pintype "bidirectional"))
      (node (ref "SW3") (pin "1") (pinfunction "P$1_1") (pintype "bidirectional"))
      (node (ref "SW4") (pin "1") (pinfunction "P$1_1") (pintype "bidirectional"))
    )
    (net (code "131") (name "Net-(SW3-P$2)") (class "Default")
      (node (ref "SJ1") (pin "2") (pinfunction "2_2") (pintype "passive"))
      (node (ref "SW3") (pin "2") (pinfunction "P$2_2") (pintype "bidirectional"))
    )
    (net (code "132") (name "Net-(SW4-P$2)") (class "Default")
      (node (ref "SJ2") (pin "2") (pinfunction "2_2") (pintype "passive"))
      (node (ref "SW4") (pin "2") (pinfunction "P$2_2") (pintype "bidirectional"))
    )
    (net (code "133") (name "Net-(T1-VOUT)") (class "Default")
      (node (ref "SJ3") (pin "1") (pinfunction "1_1") (pintype "passive"))
      (node (ref "T1") (pin "1") (pinfunction "VOUT_1") (pintype "passive"))
    )
    (net (code "134") (name "OBC_COM1") (class "Default")
      (node (ref "C102") (pin "P$7") (pinfunction "7_P$7") (pintype "passive"))
      (node (ref "C103") (pin "P$7") (pinfunction "7_P$7") (pintype "passive"))
    )
    (net (code "135") (name "OBC_COM2") (class "Default")
      (node (ref "C102") (pin "P$8") (pinfunction "8_P$8") (pintype "passive"))
      (node (ref "C103") (pin "P$8") (pinfunction "8_P$8") (pintype "passive"))
    )
    (net (code "136") (name "OBC_COM3") (class "Default")
      (node (ref "C102") (pin "P$43") (pinfunction "43_P$43") (pintype "passive"))
      (node (ref "C103") (pin "P$43") (pinfunction "43_P$43") (pintype "passive"))
    )
    (net (code "137") (name "OBC_COM4") (class "Default")
      (node (ref "C102") (pin "P$44") (pinfunction "44_P$44") (pintype "passive"))
      (node (ref "C103") (pin "P$44") (pinfunction "44_P$44") (pintype "passive"))
    )
    (net (code "138") (name "OBC_COM5") (class "Default")
      (node (ref "C102") (pin "P$45") (pinfunction "45_P$45") (pintype "passive"))
      (node (ref "C103") (pin "P$45") (pinfunction "45_P$45") (pintype "passive"))
    )
    (net (code "139") (name "OBC_COM6") (class "Default")
      (node (ref "C102") (pin "P$46") (pinfunction "46_P$46") (pintype "passive"))
      (node (ref "C103") (pin "P$46") (pinfunction "46_P$46") (pintype "passive"))
    )
    (net (code "140") (name "OBC_COM7") (class "Default")
      (node (ref "C102") (pin "P$47") (pinfunction "47_P$47") (pintype "passive"))
      (node (ref "C103") (pin "P$47") (pinfunction "47_P$47") (pintype "passive"))
    )
    (net (code "141") (name "OBC_COM8") (class "Default")
      (node (ref "C102") (pin "P$48") (pinfunction "48_P$48") (pintype "passive"))
      (node (ref "C103") (pin "P$48") (pinfunction "48_P$48") (pintype "passive"))
    )
    (net (code "142") (name "PROG_1") (class "Default")
      (node (ref "C101") (pin "P$1") (pinfunction "1_P$1") (pintype "passive"))
      (node (ref "C102") (pin "P$1") (pinfunction "1_P$1") (pintype "passive"))
    )
    (net (code "143") (name "PROG_2") (class "Default")
      (node (ref "C101") (pin "P$2") (pinfunction "2_P$2") (pintype "passive"))
      (node (ref "C102") (pin "P$2") (pinfunction "2_P$2") (pintype "passive"))
    )
    (net (code "144") (name "PROG_3") (class "Default")
      (node (ref "C101") (pin "P$3") (pinfunction "3_P$3") (pintype "passive"))
      (node (ref "C102") (pin "P$3") (pinfunction "3_P$3") (pintype "passive"))
    )
    (net (code "145") (name "PROG_4") (class "Default")
      (node (ref "C101") (pin "P$4") (pinfunction "4_P$4") (pintype "passive"))
      (node (ref "C102") (pin "P$4") (pinfunction "4_P$4") (pintype "passive"))
    )
    (net (code "146") (name "PROG_5") (class "Default")
      (node (ref "C101") (pin "P$5") (pinfunction "5_P$5") (pintype "passive"))
      (node (ref "C102") (pin "P$5") (pinfunction "5_P$5") (pintype "passive"))
    )
    (net (code "147") (name "PROG_6") (class "Default")
      (node (ref "C101") (pin "P$6") (pinfunction "6_P$6") (pintype "passive"))
      (node (ref "C102") (pin "P$6") (pinfunction "6_P$6") (pintype "passive"))
    )
    (net (code "148") (name "PWR_SC_+X") (class "Default")
      (node (ref "C101") (pin "P$27") (pinfunction "27_P$27") (pintype "passive"))
      (node (ref "SP1") (pin "8") (pinfunction "8_8") (pintype "passive"))
      (node (ref "SP1") (pin "9") (pinfunction "9_9") (pintype "passive"))
    )
    (net (code "149") (name "PWR_SC_+Y") (class "Default")
      (node (ref "C101") (pin "P$37") (pinfunction "37_P$37") (pintype "passive"))
      (node (ref "SP3") (pin "8") (pinfunction "8_8") (pintype "passive"))
      (node (ref "SP3") (pin "9") (pinfunction "9_9") (pintype "passive"))
    )
    (net (code "150") (name "PWR_SC_-X") (class "Default")
      (node (ref "C101") (pin "P$31") (pinfunction "31_P$31") (pintype "passive"))
      (node (ref "SP2") (pin "8") (pinfunction "8_8") (pintype "passive"))
      (node (ref "SP2") (pin "9") (pinfunction "9_9") (pintype "passive"))
    )
    (net (code "151") (name "PWR_SC_-Y") (class "Default")
      (node (ref "C101") (pin "P$21") (pinfunction "21_P$21") (pintype "passive"))
      (node (ref "SP4") (pin "8") (pinfunction "8_8") (pintype "passive"))
      (node (ref "SP4") (pin "9") (pinfunction "9_9") (pintype "passive"))
    )
    (net (code "152") (name "PWR_SC_-Z") (class "Default")
      (node (ref "C101") (pin "P$33") (pinfunction "33_P$33") (pintype "passive"))
      (node (ref "SP5") (pin "8") (pinfunction "8_8") (pintype "passive"))
      (node (ref "SP5") (pin "9") (pinfunction "9_9") (pintype "passive"))
    )
    (net (code "153") (name "RAW_POWER") (class "Default")
      (node (ref "C101") (pin "P$29") (pinfunction "29_P$29") (pintype "passive"))
      (node (ref "C101") (pin "P$30") (pinfunction "30_P$30") (pintype "passive"))
      (node (ref "C102") (pin "P$29") (pinfunction "29_P$29") (pintype "passive"))
      (node (ref "C102") (pin "P$30") (pinfunction "30_P$30") (pintype "passive"))
      (node (ref "R5") (pin "1") (pinfunction "1_1") (pintype "passive"))
      (node (ref "R7") (pin "1") (pinfunction "1_1") (pintype "passive"))
    )
    (net (code "154") (name "SP_BUS_1") (class "Default")
      (node (ref "SJ9") (pin "1") (pinfunction "1_1") (pintype "passive"))
      (node (ref "SP1") (pin "4") (pinfunction "4_4") (pintype "passive"))
      (node (ref "SP2") (pin "4") (pinfunction "4_4") (pintype "passive"))
      (node (ref "SP3") (pin "4") (pinfunction "4_4") (pintype "passive"))
      (node (ref "SP4") (pin "4") (pinfunction "4_4") (pintype "passive"))
      (node (ref "SP5") (pin "4") (pinfunction "4_4") (pintype "passive"))
    )
    (net (code "155") (name "SP_BUS_2") (class "Default")
      (node (ref "SJ10") (pin "1") (pinfunction "1_1") (pintype "passive"))
      (node (ref "SP1") (pin "5") (pinfunction "5_5") (pintype "passive"))
      (node (ref "SP2") (pin "5") (pinfunction "5_5") (pintype "passive"))
      (node (ref "SP3") (pin "5") (pinfunction "5_5") (pintype "passive"))
      (node (ref "SP4") (pin "5") (pinfunction "5_5") (pintype "passive"))
      (node (ref "SP5") (pin "5") (pinfunction "5_5") (pintype "passive"))
    )
    (net (code "156") (name "SUP5V0") (class "Default")
      (node (ref "C101") (pin "P$15") (pinfunction "15_P$15") (pintype "passive"))
      (node (ref "C101") (pin "P$16") (pinfunction "16_P$16") (pintype "passive"))
      (node (ref "C102") (pin "P$15") (pinfunction "15_P$15") (pintype "passive"))
      (node (ref "C102") (pin "P$16") (pinfunction "16_P$16") (pintype "passive"))
      (node (ref "C103") (pin "P$15") (pinfunction "15_P$15") (pintype "passive"))
      (node (ref "C103") (pin "P$16") (pinfunction "16_P$16") (pintype "passive"))
      (node (ref "C104") (pin "P$15") (pinfunction "15_P$15") (pintype "passive"))
      (node (ref "C104") (pin "P$16") (pinfunction "16_P$16") (pintype "passive"))
      (node (ref "C105") (pin "P$15") (pinfunction "15_P$15") (pintype "passive"))
      (node (ref "C105") (pin "P$16") (pinfunction "16_P$16") (pintype "passive"))
      (node (ref "C106") (pin "P$15") (pinfunction "15_P$15") (pintype "passive"))
      (node (ref "C106") (pin "P$16") (pinfunction "16_P$16") (pintype "passive"))
    )
    (net (code "157") (name "SUP_3V3_1") (class "Default")
      (node (ref "C101") (pin "P$49") (pinfunction "49_P$49") (pintype "passive"))
      (node (ref "C101") (pin "P$50") (pinfunction "50_P$50") (pintype "passive"))
      (node (ref "C102") (pin "P$49") (pinfunction "49_P$49") (pintype "passive"))
      (node (ref "C102") (pin "P$50") (pinfunction "50_P$50") (pintype "passive"))
      (node (ref "C103") (pin "P$49") (pinfunction "49_P$49") (pintype "passive"))
      (node (ref "C103") (pin "P$50") (pinfunction "50_P$50") (pintype "passive"))
      (node (ref "C104") (pin "P$49") (pinfunction "49_P$49") (pintype "passive"))
      (node (ref "C104") (pin "P$50") (pinfunction "50_P$50") (pintype "passive"))
      (node (ref "C105") (pin "P$49") (pinfunction "49_P$49") (pintype "passive"))
      (node (ref "C105") (pin "P$50") (pinfunction "50_P$50") (pintype "passive"))
      (node (ref "C106") (pin "P$49") (pinfunction "49_P$49") (pintype "passive"))
      (node (ref "C106") (pin "P$50") (pinfunction "50_P$50") (pintype "passive"))
      (node (ref "C7") (pin "1") (pinfunction "1_1") (pintype "passive"))
      (node (ref "SP1") (pin "2") (pinfunction "2_2") (pintype "passive"))
      (node (ref "SP2") (pin "2") (pinfunction "2_2") (pintype "passive"))
      (node (ref "SP3") (pin "2") (pinfunction "2_2") (pintype "passive"))
      (node (ref "SP4") (pin "2") (pinfunction "2_2") (pintype "passive"))
      (node (ref "SP5") (pin "2") (pinfunction "2_2") (pintype "passive"))
      (node (ref "T1") (pin "5") (pinfunction "~_5") (pintype "passive"))
      (node (ref "T1") (pin "8") (pinfunction "+VS_8") (pintype "power_in"))
    )
    (net (code "158") (name "SUP_3V3_2") (class "Default")
      (node (ref "C101") (pin "P$25") (pinfunction "25_P$25") (pintype "passive"))
      (node (ref "C101") (pin "P$26") (pinfunction "26_P$26") (pintype "passive"))
      (node (ref "C102") (pin "P$25") (pinfunction "25_P$25") (pintype "passive"))
      (node (ref "C102") (pin "P$26") (pinfunction "26_P$26") (pintype "passive"))
      (node (ref "C103") (pin "P$25") (pinfunction "25_P$25") (pintype "passive"))
      (node (ref "C103") (pin "P$26") (pinfunction "26_P$26") (pintype "passive"))
      (node (ref "C104") (pin "P$25") (pinfunction "25_P$25") (pintype "passive"))
      (node (ref "C104") (pin "P$26") (pinfunction "26_P$26") (pintype "passive"))
      (node (ref "C105") (pin "P$25") (pinfunction "25_P$25") (pintype "passive"))
      (node (ref "C105") (pin "P$26") (pinfunction "26_P$26") (pintype "passive"))
      (node (ref "C106") (pin "P$25") (pinfunction "25_P$25") (pintype "passive"))
      (node (ref "C106") (pin "P$26") (pinfunction "26_P$26") (pintype "passive"))
      (node (ref "C5") (pin "1") (pinfunction "1_1") (pintype "passive"))
      (node (ref "DC1V8") (pin "3") (pinfunction "3_3") (pintype "bidirectional"))
      (node (ref "IC2") (pin "106") (pinfunction "VCCO1_106") (pintype "power_in"))
      (node (ref "IC2") (pin "119") (pinfunction "VCCO1_119") (pintype "power_in"))
      (node (ref "IC2") (pin "136") (pinfunction "VCCO0_136") (pintype "power_in"))
      (node (ref "IC2") (pin "19") (pinfunction "VCCO0_19") (pintype "power_in"))
      (node (ref "IC2") (pin "3") (pinfunction "VCCO0_3") (pintype "power_in"))
      (node (ref "IC2") (pin "34") (pinfunction "VCCO0_34") (pintype "power_in"))
      (node (ref "IC2") (pin "47") (pinfunction "VCCO0_47") (pintype "power_in"))
      (node (ref "IC2") (pin "64") (pinfunction "VCCO1_64") (pintype "power_in"))
      (node (ref "IC2") (pin "75") (pinfunction "VCCO1_75") (pintype "power_in"))
      (node (ref "IC2") (pin "91") (pinfunction "VCCO1_91") (pintype "power_in"))
      (node (ref "JTAG") (pin "1") (pinfunction "1_1") (pintype "passive"))
      (node (ref "R1") (pin "2") (pinfunction "2_2") (pintype "passive"))
      (node (ref "R2") (pin "2") (pinfunction "2_2") (pintype "passive"))
      (node (ref "R3") (pin "2") (pinfunction "2_2") (pintype "passive"))
    )
    (net (code "159") (name "SUP_UNREG_1") (class "Default")
      (node (ref "C101") (pin "P$23") (pinfunction "23_P$23") (pintype "passive"))
      (node (ref "C101") (pin "P$24") (pinfunction "24_P$24") (pintype "passive"))
      (node (ref "C102") (pin "P$23") (pinfunction "23_P$23") (pintype "passive"))
      (node (ref "C102") (pin "P$24") (pinfunction "24_P$24") (pintype "passive"))
      (node (ref "C103") (pin "P$23") (pinfunction "23_P$23") (pintype "passive"))
      (node (ref "C103") (pin "P$24") (pinfunction "24_P$24") (pintype "passive"))
      (node (ref "C104") (pin "P$23") (pinfunction "23_P$23") (pintype "passive"))
      (node (ref "C104") (pin "P$24") (pinfunction "24_P$24") (pintype "passive"))
      (node (ref "C105") (pin "P$23") (pinfunction "23_P$23") (pintype "passive"))
      (node (ref "C105") (pin "P$24") (pinfunction "24_P$24") (pintype "passive"))
      (node (ref "C106") (pin "P$23") (pinfunction "23_P$23") (pintype "passive"))
      (node (ref "C106") (pin "P$24") (pinfunction "24_P$24") (pintype "passive"))
    )
    (net (code "160") (name "SUP_UNREG_2") (class "Default")
      (node (ref "C101") (pin "P$35") (pinfunction "35_P$35") (pintype "passive"))
      (node (ref "C101") (pin "P$36") (pinfunction "36_P$36") (pintype "passive"))
      (node (ref "C102") (pin "P$35") (pinfunction "35_P$35") (pintype "passive"))
      (node (ref "C102") (pin "P$36") (pinfunction "36_P$36") (pintype "passive"))
      (node (ref "C103") (pin "P$35") (pinfunction "35_P$35") (pintype "passive"))
      (node (ref "C103") (pin "P$36") (pinfunction "36_P$36") (pintype "passive"))
      (node (ref "C104") (pin "P$35") (pinfunction "35_P$35") (pintype "passive"))
      (node (ref "C104") (pin "P$36") (pinfunction "36_P$36") (pintype "passive"))
      (node (ref "C105") (pin "P$35") (pinfunction "35_P$35") (pintype "passive"))
      (node (ref "C105") (pin "P$36") (pinfunction "36_P$36") (pintype "passive"))
      (node (ref "C106") (pin "P$35") (pinfunction "35_P$35") (pintype "passive"))
      (node (ref "C106") (pin "P$36") (pinfunction "36_P$36") (pintype "passive"))
    )
    (net (code "161") (name "TEMP_+X") (class "Default")
      (node (ref "C101") (pin "P$28") (pinfunction "28_P$28") (pintype "passive"))
      (node (ref "SP1") (pin "10") (pinfunction "10_10") (pintype "passive"))
    )
    (net (code "162") (name "TEMP_+Y") (class "Default")
      (node (ref "C101") (pin "P$38") (pinfunction "38_P$38") (pintype "passive"))
      (node (ref "SP3") (pin "10") (pinfunction "10_10") (pintype "passive"))
    )
    (net (code "163") (name "TEMP_-X") (class "Default")
      (node (ref "C101") (pin "P$32") (pinfunction "32_P$32") (pintype "passive"))
      (node (ref "SP2") (pin "10") (pinfunction "10_10") (pintype "passive"))
    )
    (net (code "164") (name "TEMP_-Y") (class "Default")
      (node (ref "C101") (pin "P$22") (pinfunction "22_P$22") (pintype "passive"))
      (node (ref "SP4") (pin "10") (pinfunction "10_10") (pintype "passive"))
    )
    (net (code "165") (name "TEMP_-Z") (class "Default")
      (node (ref "C101") (pin "P$34") (pinfunction "34_P$34") (pintype "passive"))
      (node (ref "SP5") (pin "10") (pinfunction "10_10") (pintype "passive"))
    )
    (net (code "166") (name "unconnected-(IC2-CLK0_I-Pad128)") (class "Default")
      (node (ref "IC2") (pin "128") (pinfunction "CLK0_I_128") (pintype "input"))
    )
    (net (code "167") (name "unconnected-(IC2-CLK1_I-Pad54)") (class "Default")
      (node (ref "IC2") (pin "54") (pinfunction "CLK1_I_54") (pintype "input"))
    )
    (net (code "168") (name "unconnected-(IC2-CLK2_I-Pad56)") (class "Default")
      (node (ref "IC2") (pin "56") (pinfunction "CLK2_I_56") (pintype "input"))
    )
    (net (code "169") (name "unconnected-(IC2-CLK3_I-Pad126)") (class "Default")
      (node (ref "IC2") (pin "126") (pinfunction "CLK3_I_126") (pintype "input"))
    )
    (net (code "170") (name "unconnected-(IC2-I0-Pad17)") (class "Default")
      (node (ref "IC2") (pin "17") (pinfunction "I0_17") (pintype "bidirectional"))
    )
    (net (code "171") (name "unconnected-(IC2-I1-Pad20)") (class "Default")
      (node (ref "IC2") (pin "20") (pinfunction "I1_20") (pintype "bidirectional"))
    )
    (net (code "172") (name "unconnected-(IC2-I2-Pad38)") (class "Default")
      (node (ref "IC2") (pin "38") (pinfunction "I2_38") (pintype "bidirectional"))
    )
    (net (code "173") (name "unconnected-(IC2-I3-Pad45)") (class "Default")
      (node (ref "IC2") (pin "45") (pinfunction "I3_45") (pintype "bidirectional"))
    )
    (net (code "174") (name "unconnected-(IC2-I4-Pad72)") (class "Default")
      (node (ref "IC2") (pin "72") (pinfunction "I4_72") (pintype "bidirectional"))
    )
    (net (code "175") (name "unconnected-(IC2-I5-Pad89)") (class "Default")
      (node (ref "IC2") (pin "89") (pinfunction "I5_89") (pintype "bidirectional"))
    )
    (net (code "176") (name "unconnected-(IC2-I6-Pad92)") (class "Default")
      (node (ref "IC2") (pin "92") (pinfunction "I6_92") (pintype "bidirectional"))
    )
    (net (code "177") (name "unconnected-(IC2-I7-Pad110)") (class "Default")
      (node (ref "IC2") (pin "110") (pinfunction "I7_110") (pintype "bidirectional"))
    )
    (net (code "178") (name "unconnected-(IC2-I8-Pad117)") (class "Default")
      (node (ref "IC2") (pin "117") (pinfunction "I8_117") (pintype "bidirectional"))
    )
    (net (code "179") (name "unconnected-(IC2-I9-Pad144)") (class "Default")
      (node (ref "IC2") (pin "144") (pinfunction "I9_144") (pintype "bidirectional"))
    )
    (net (code "180") (name "unconnected-(IC2-IOA2_GOE0-Pad130)") (class "Default")
      (node (ref "IC2") (pin "130") (pinfunction "IOA2_GOE0_130") (pintype "bidirectional"))
    )
    (net (code "181") (name "unconnected-(IC2-IOP2_GOE1-Pad125)") (class "Default")
      (node (ref "IC2") (pin "125") (pinfunction "IOP2_GOE1_125") (pintype "bidirectional"))
    )
    (net (code "182") (name "unconnected-(IC2-NC0-Pad18)") (class "Default")
      (node (ref "IC2") (pin "18") (pinfunction "NC0_18") (pintype "passive"))
    )
    (net (code "183") (name "unconnected-(IC2-NC1-Pad90)") (class "Default")
      (node (ref "IC2") (pin "90") (pinfunction "NC1_90") (pintype "passive"))
    )
    (net (code "184") (name "unconnected-(SP1-Pad3)") (class "Default")
      (node (ref "SP1") (pin "3") (pinfunction "3_3") (pintype "passive"))
    )
    (net (code "185") (name "unconnected-(SP1-Pad6)") (class "Default")
      (node (ref "SP1") (pin "6") (pinfunction "6_6") (pintype "passive"))
    )
    (net (code "186") (name "unconnected-(SP1-Pad7)") (class "Default")
      (node (ref "SP1") (pin "7") (pinfunction "7_7") (pintype "passive"))
    )
    (net (code "187") (name "unconnected-(SP1-Pad11)") (class "Default")
      (node (ref "SP1") (pin "11") (pinfunction "11_11") (pintype "passive"))
    )
    (net (code "188") (name "unconnected-(SP2-Pad3)") (class "Default")
      (node (ref "SP2") (pin "3") (pinfunction "3_3") (pintype "passive"))
    )
    (net (code "189") (name "unconnected-(SP2-Pad6)") (class "Default")
      (node (ref "SP2") (pin "6") (pinfunction "6_6") (pintype "passive"))
    )
    (net (code "190") (name "unconnected-(SP2-Pad7)") (class "Default")
      (node (ref "SP2") (pin "7") (pinfunction "7_7") (pintype "passive"))
    )
    (net (code "191") (name "unconnected-(SP2-Pad11)") (class "Default")
      (node (ref "SP2") (pin "11") (pinfunction "11_11") (pintype "passive"))
    )
    (net (code "192") (name "unconnected-(SP3-Pad3)") (class "Default")
      (node (ref "SP3") (pin "3") (pinfunction "3_3") (pintype "passive"))
    )
    (net (code "193") (name "unconnected-(SP3-Pad6)") (class "Default")
      (node (ref "SP3") (pin "6") (pinfunction "6_6") (pintype "passive"))
    )
    (net (code "194") (name "unconnected-(SP3-Pad7)") (class "Default")
      (node (ref "SP3") (pin "7") (pinfunction "7_7") (pintype "passive"))
    )
    (net (code "195") (name "unconnected-(SP3-Pad11)") (class "Default")
      (node (ref "SP3") (pin "11") (pinfunction "11_11") (pintype "passive"))
    )
    (net (code "196") (name "unconnected-(SP4-Pad3)") (class "Default")
      (node (ref "SP4") (pin "3") (pinfunction "3_3") (pintype "passive"))
    )
    (net (code "197") (name "unconnected-(SP4-Pad11)") (class "Default")
      (node (ref "SP4") (pin "11") (pinfunction "11_11") (pintype "passive"))
    )
    (net (code "198") (name "unconnected-(SP5-Pad3)") (class "Default")
      (node (ref "SP5") (pin "3") (pinfunction "3_3") (pintype "passive"))
    )
    (net (code "199") (name "unconnected-(SP5-Pad11)") (class "Default")
      (node (ref "SP5") (pin "11") (pinfunction "11_11") (pintype "passive"))
    )
    (net (code "200") (name "unconnected-(T1-NC-Pad7)") (class "Default")
      (node (ref "T1") (pin "7") (pinfunction "NC_7") (pintype "passive"))
    )
    (net (code "201") (name "unconnected-(T1-NC_2-Pad2)") (class "Default")
      (node (ref "T1") (pin "2") (pinfunction "NC_2_2") (pintype "passive"))
    )
    (net (code "202") (name "unconnected-(T1-NC_3-Pad3)") (class "Default")
      (node (ref "T1") (pin "3") (pinfunction "NC_3_3") (pintype "passive"))
    )
    (net (code "203") (name "unconnected-(T1-NC_4-Pad6)") (class "Default")
      (node (ref "T1") (pin "6") (pinfunction "NC_4_6") (pintype "passive"))
    )
  )
)
